# Configuration_JTAG.net
KiCad netlist of a schematic drawn in Altium Designer
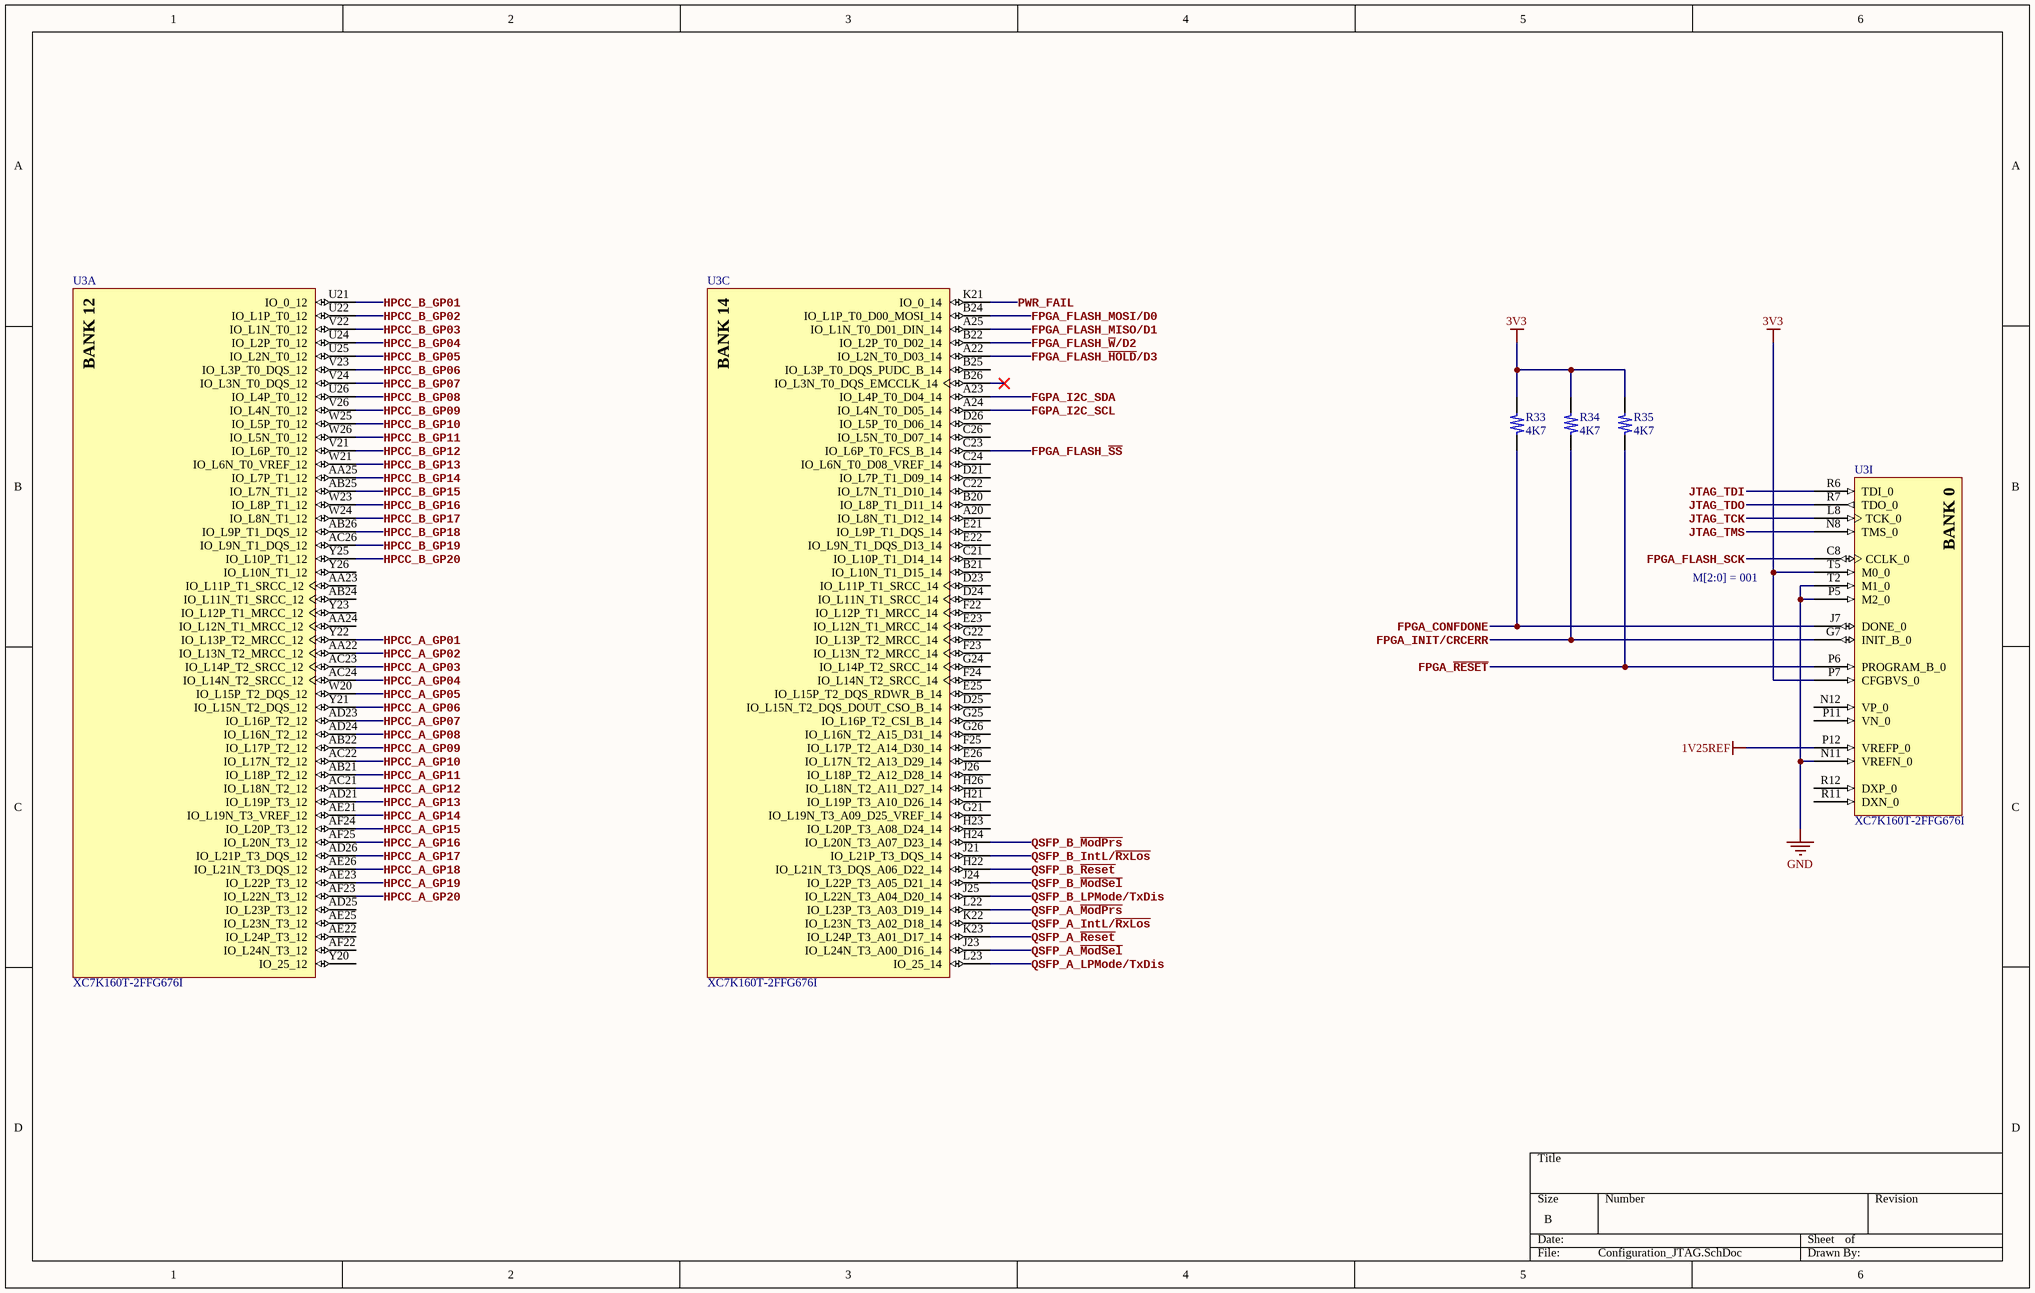
[diagram p0: Configuration_JTAG.SchDoc]

(export (version "E")
  (design (tool "Eeschema 10.0.6"))
  (components
    (comp (ref "R33")
      (value "4K7")
      (footprint "R_0402_Generic")
      (description "RES 4.7K OHM 1% 1/16W 0402")
      (libsource (lib "Capstone_Schematic_Library") (part "R_0402_Generic"))
    )
    (comp (ref "R34")
      (value "4K7")
      (footprint "R_0402_Generic")
      (description "RES 4.7K OHM 1% 1/16W 0402")
      (libsource (lib "Capstone_Schematic_Library") (part "R_0402_Generic"))
    )
    (comp (ref "R35")
      (value "4K7")
      (footprint "R_0402_Generic")
      (description "RES 4.7K OHM 1% 1/16W 0402")
      (libsource (lib "Capstone_Schematic_Library") (part "R_0402_Generic"))
    )
    (comp (ref "U3")
      (value "XC7K160T-2FFG676I")
      (footprint "FFG676_(XC7K160T-2FFG676I)")
      (description "Kintex-7 FPGA, 400 User I/Os, 8 GTX, 676-Ball BGA, Speed Grade 2, Industrial Grade, Pb-Free")
      (fields (field (name "GENERIC PART NUMBER") "XC7K160T") (field (name "MANUFACTURER") "Xilinx"))
      (libsource (lib "Capstone_Schematic_Library") (part "XC7K160T"))
    )
  )
  (nets
    (net (code "1") (name "/FGPA_I2C_SCL") (class "Default")
      (node (ref "U3") (pin "A24") (pinfunction "IO_L4N_T0_D05_14_A24") (pintype "bidirectional"))
    )
    (net (code "2") (name "/FGPA_I2C_SDA") (class "Default")
      (node (ref "U3") (pin "A23") (pinfunction "IO_L4P_T0_D04_14_A23") (pintype "bidirectional"))
    )
    (net (code "3") (name "/FPGA_CONFDONE") (class "Default")
      (node (ref "R33") (pin "1") (pinfunction "1_1") (pintype "passive"))
      (node (ref "U3") (pin "J7") (pinfunction "DONE_0_J7") (pintype "bidirectional"))
    )
    (net (code "4") (name "/FPGA_FLASH_MISO{slash}D1") (class "Default")
      (node (ref "U3") (pin "A25") (pinfunction "IO_L1N_T0_D01_DIN_14_A25") (pintype "bidirectional"))
    )
    (net (code "5") (name "/FPGA_FLASH_MOSI{slash}D0") (class "Default")
      (node (ref "U3") (pin "B24") (pinfunction "IO_L1P_T0_D00_MOSI_14_B24") (pintype "bidirectional"))
    )
    (net (code "6") (name "/FPGA_FLASH_SCK") (class "Default")
      (node (ref "U3") (pin "C8") (pinfunction "CCLK_0_C8") (pintype "bidirectional"))
    )
    (net (code "7") (name "/FPGA_FLASH_~{HOLD}{slash}D3") (class "Default")
      (node (ref "U3") (pin "A22") (pinfunction "IO_L2N_T0_D03_14_A22") (pintype "bidirectional"))
    )
    (net (code "8") (name "/FPGA_FLASH_~{SS}") (class "Default")
      (node (ref "U3") (pin "C23") (pinfunction "IO_L6P_T0_FCS_B_14_C23") (pintype "bidirectional"))
    )
    (net (code "9") (name "/FPGA_FLASH_~{W}{slash}D2") (class "Default")
      (node (ref "U3") (pin "B22") (pinfunction "IO_L2P_T0_D02_14_B22") (pintype "bidirectional"))
    )
    (net (code "10") (name "/FPGA_INIT{slash}CRCERR") (class "Default")
      (node (ref "R34") (pin "1") (pinfunction "1_1") (pintype "passive"))
      (node (ref "U3") (pin "G7") (pinfunction "INIT_B_0_G7") (pintype "bidirectional"))
    )
    (net (code "11") (name "/FPGA_~{RESET}") (class "Default")
      (node (ref "R35") (pin "1") (pinfunction "1_1") (pintype "passive"))
      (node (ref "U3") (pin "P6") (pinfunction "PROGRAM_B_0_P6") (pintype "input"))
    )
    (net (code "12") (name "/HPCC_A_GP01") (class "Default")
      (node (ref "U3") (pin "Y22") (pinfunction "IO_L13P_T2_MRCC_12_Y22") (pintype "bidirectional"))
    )
    (net (code "13") (name "/HPCC_A_GP02") (class "Default")
      (node (ref "U3") (pin "AA22") (pinfunction "IO_L13N_T2_MRCC_12_AA22") (pintype "bidirectional"))
    )
    (net (code "14") (name "/HPCC_A_GP03") (class "Default")
      (node (ref "U3") (pin "AC23") (pinfunction "IO_L14P_T2_SRCC_12_AC23") (pintype "bidirectional"))
    )
    (net (code "15") (name "/HPCC_A_GP04") (class "Default")
      (node (ref "U3") (pin "AC24") (pinfunction "IO_L14N_T2_SRCC_12_AC24") (pintype "bidirectional"))
    )
    (net (code "16") (name "/HPCC_A_GP05") (class "Default")
      (node (ref "U3") (pin "W20") (pinfunction "IO_L15P_T2_DQS_12_W20") (pintype "bidirectional"))
    )
    (net (code "17") (name "/HPCC_A_GP06") (class "Default")
      (node (ref "U3") (pin "Y21") (pinfunction "IO_L15N_T2_DQS_12_Y21") (pintype "bidirectional"))
    )
    (net (code "18") (name "/HPCC_A_GP07") (class "Default")
      (node (ref "U3") (pin "AD23") (pinfunction "IO_L16P_T2_12_AD23") (pintype "bidirectional"))
    )
    (net (code "19") (name "/HPCC_A_GP08") (class "Default")
      (node (ref "U3") (pin "AD24") (pinfunction "IO_L16N_T2_12_AD24") (pintype "bidirectional"))
    )
    (net (code "20") (name "/HPCC_A_GP09") (class "Default")
      (node (ref "U3") (pin "AB22") (pinfunction "IO_L17P_T2_12_AB22") (pintype "bidirectional"))
    )
    (net (code "21") (name "/HPCC_A_GP10") (class "Default")
      (node (ref "U3") (pin "AC22") (pinfunction "IO_L17N_T2_12_AC22") (pintype "bidirectional"))
    )
    (net (code "22") (name "/HPCC_A_GP11") (class "Default")
      (node (ref "U3") (pin "AB21") (pinfunction "IO_L18P_T2_12_AB21") (pintype "bidirectional"))
    )
    (net (code "23") (name "/HPCC_A_GP12") (class "Default")
      (node (ref "U3") (pin "AC21") (pinfunction "IO_L18N_T2_12_AC21") (pintype "bidirectional"))
    )
    (net (code "24") (name "/HPCC_A_GP13") (class "Default")
      (node (ref "U3") (pin "AD21") (pinfunction "IO_L19P_T3_12_AD21") (pintype "bidirectional"))
    )
    (net (code "25") (name "/HPCC_A_GP14") (class "Default")
      (node (ref "U3") (pin "AE21") (pinfunction "IO_L19N_T3_VREF_12_AE21") (pintype "bidirectional"))
    )
    (net (code "26") (name "/HPCC_A_GP15") (class "Default")
      (node (ref "U3") (pin "AF24") (pinfunction "IO_L20P_T3_12_AF24") (pintype "bidirectional"))
    )
    (net (code "27") (name "/HPCC_A_GP16") (class "Default")
      (node (ref "U3") (pin "AF25") (pinfunction "IO_L20N_T3_12_AF25") (pintype "bidirectional"))
    )
    (net (code "28") (name "/HPCC_A_GP17") (class "Default")
      (node (ref "U3") (pin "AD26") (pinfunction "IO_L21P_T3_DQS_12_AD26") (pintype "bidirectional"))
    )
    (net (code "29") (name "/HPCC_A_GP18") (class "Default")
      (node (ref "U3") (pin "AE26") (pinfunction "IO_L21N_T3_DQS_12_AE26") (pintype "bidirectional"))
    )
    (net (code "30") (name "/HPCC_A_GP19") (class "Default")
      (node (ref "U3") (pin "AE23") (pinfunction "IO_L22P_T3_12_AE23") (pintype "bidirectional"))
    )
    (net (code "31") (name "/HPCC_A_GP20") (class "Default")
      (node (ref "U3") (pin "AF23") (pinfunction "IO_L22N_T3_12_AF23") (pintype "bidirectional"))
    )
    (net (code "32") (name "/HPCC_B_GP01") (class "Default")
      (node (ref "U3") (pin "U21") (pinfunction "IO_0_12_U21") (pintype "bidirectional"))
    )
    (net (code "33") (name "/HPCC_B_GP02") (class "Default")
      (node (ref "U3") (pin "U22") (pinfunction "IO_L1P_T0_12_U22") (pintype "bidirectional"))
    )
    (net (code "34") (name "/HPCC_B_GP03") (class "Default")
      (node (ref "U3") (pin "V22") (pinfunction "IO_L1N_T0_12_V22") (pintype "bidirectional"))
    )
    (net (code "35") (name "/HPCC_B_GP04") (class "Default")
      (node (ref "U3") (pin "U24") (pinfunction "IO_L2P_T0_12_U24") (pintype "bidirectional"))
    )
    (net (code "36") (name "/HPCC_B_GP05") (class "Default")
      (node (ref "U3") (pin "U25") (pinfunction "IO_L2N_T0_12_U25") (pintype "bidirectional"))
    )
    (net (code "37") (name "/HPCC_B_GP06") (class "Default")
      (node (ref "U3") (pin "V23") (pinfunction "IO_L3P_T0_DQS_12_V23") (pintype "bidirectional"))
    )
    (net (code "38") (name "/HPCC_B_GP07") (class "Default")
      (node (ref "U3") (pin "V24") (pinfunction "IO_L3N_T0_DQS_12_V24") (pintype "bidirectional"))
    )
    (net (code "39") (name "/HPCC_B_GP08") (class "Default")
      (node (ref "U3") (pin "U26") (pinfunction "IO_L4P_T0_12_U26") (pintype "bidirectional"))
    )
    (net (code "40") (name "/HPCC_B_GP09") (class "Default")
      (node (ref "U3") (pin "V26") (pinfunction "IO_L4N_T0_12_V26") (pintype "bidirectional"))
    )
    (net (code "41") (name "/HPCC_B_GP10") (class "Default")
      (node (ref "U3") (pin "W25") (pinfunction "IO_L5P_T0_12_W25") (pintype "bidirectional"))
    )
    (net (code "42") (name "/HPCC_B_GP11") (class "Default")
      (node (ref "U3") (pin "W26") (pinfunction "IO_L5N_T0_12_W26") (pintype "bidirectional"))
    )
    (net (code "43") (name "/HPCC_B_GP12") (class "Default")
      (node (ref "U3") (pin "V21") (pinfunction "IO_L6P_T0_12_V21") (pintype "bidirectional"))
    )
    (net (code "44") (name "/HPCC_B_GP13") (class "Default")
      (node (ref "U3") (pin "W21") (pinfunction "IO_L6N_T0_VREF_12_W21") (pintype "bidirectional"))
    )
    (net (code "45") (name "/HPCC_B_GP14") (class "Default")
      (node (ref "U3") (pin "AA25") (pinfunction "IO_L7P_T1_12_AA25") (pintype "bidirectional"))
    )
    (net (code "46") (name "/HPCC_B_GP15") (class "Default")
      (node (ref "U3") (pin "AB25") (pinfunction "IO_L7N_T1_12_AB25") (pintype "bidirectional"))
    )
    (net (code "47") (name "/HPCC_B_GP16") (class "Default")
      (node (ref "U3") (pin "W23") (pinfunction "IO_L8P_T1_12_W23") (pintype "bidirectional"))
    )
    (net (code "48") (name "/HPCC_B_GP17") (class "Default")
      (node (ref "U3") (pin "W24") (pinfunction "IO_L8N_T1_12_W24") (pintype "bidirectional"))
    )
    (net (code "49") (name "/HPCC_B_GP18") (class "Default")
      (node (ref "U3") (pin "AB26") (pinfunction "IO_L9P_T1_DQS_12_AB26") (pintype "bidirectional"))
    )
    (net (code "50") (name "/HPCC_B_GP19") (class "Default")
      (node (ref "U3") (pin "AC26") (pinfunction "IO_L9N_T1_DQS_12_AC26") (pintype "bidirectional"))
    )
    (net (code "51") (name "/HPCC_B_GP20") (class "Default")
      (node (ref "U3") (pin "Y25") (pinfunction "IO_L10P_T1_12_Y25") (pintype "bidirectional"))
    )
    (net (code "52") (name "/JTAG_TCK") (class "Default")
      (node (ref "U3") (pin "L8") (pinfunction "TCK_0_L8") (pintype "input"))
    )
    (net (code "53") (name "/JTAG_TDI") (class "Default")
      (node (ref "U3") (pin "R6") (pinfunction "TDI_0_R6") (pintype "input"))
    )
    (net (code "54") (name "/JTAG_TDO") (class "Default")
      (node (ref "U3") (pin "R7") (pinfunction "TDO_0_R7") (pintype "output"))
    )
    (net (code "55") (name "/JTAG_TMS") (class "Default")
      (node (ref "U3") (pin "N8") (pinfunction "TMS_0_N8") (pintype "input"))
    )
    (net (code "56") (name "/PWR_FAIL") (class "Default")
      (node (ref "U3") (pin "K21") (pinfunction "IO_0_14_K21") (pintype "bidirectional"))
    )
    (net (code "57") (name "/QSFP_A_IntL{slash}~{RxLos}") (class "Default")
      (node (ref "U3") (pin "K22") (pinfunction "IO_L23N_T3_A02_D18_14_K22") (pintype "bidirectional"))
    )
    (net (code "58") (name "/QSFP_A_LPMode{slash}TxDis") (class "Default")
      (node (ref "U3") (pin "L23") (pinfunction "IO_25_14_L23") (pintype "bidirectional"))
    )
    (net (code "59") (name "/QSFP_A_~{ModPrs}") (class "Default")
      (node (ref "U3") (pin "L22") (pinfunction "IO_L23P_T3_A03_D19_14_L22") (pintype "bidirectional"))
    )
    (net (code "60") (name "/QSFP_A_~{ModSel}") (class "Default")
      (node (ref "U3") (pin "J23") (pinfunction "IO_L24N_T3_A00_D16_14_J23") (pintype "bidirectional"))
    )
    (net (code "61") (name "/QSFP_A_~{Reset}") (class "Default")
      (node (ref "U3") (pin "K23") (pinfunction "IO_L24P_T3_A01_D17_14_K23") (pintype "bidirectional"))
    )
    (net (code "62") (name "/QSFP_B_IntL{slash}~{RxLos}") (class "Default")
      (node (ref "U3") (pin "J21") (pinfunction "IO_L21P_T3_DQS_14_J21") (pintype "bidirectional"))
    )
    (net (code "63") (name "/QSFP_B_LPMode{slash}TxDis") (class "Default")
      (node (ref "U3") (pin "J25") (pinfunction "IO_L22N_T3_A04_D20_14_J25") (pintype "bidirectional"))
    )
    (net (code "64") (name "/QSFP_B_~{ModPrs}") (class "Default")
      (node (ref "U3") (pin "H24") (pinfunction "IO_L20N_T3_A07_D23_14_H24") (pintype "bidirectional"))
    )
    (net (code "65") (name "/QSFP_B_~{ModSel}") (class "Default")
      (node (ref "U3") (pin "J24") (pinfunction "IO_L22P_T3_A05_D21_14_J24") (pintype "bidirectional"))
    )
    (net (code "66") (name "/QSFP_B_~{Reset}") (class "Default")
      (node (ref "U3") (pin "H22") (pinfunction "IO_L21N_T3_DQS_A06_D22_14_H22") (pintype "bidirectional"))
    )
    (net (code "67") (name "1V25REF") (class "Default")
      (node (ref "U3") (pin "P12") (pinfunction "VREFP_0_P12") (pintype "input"))
    )
    (net (code "68") (name "3V3") (class "Default")
      (node (ref "R33") (pin "2") (pinfunction "2_2") (pintype "passive"))
      (node (ref "R34") (pin "2") (pinfunction "2_2") (pintype "passive"))
      (node (ref "R35") (pin "2") (pinfunction "2_2") (pintype "passive"))
      (node (ref "U3") (pin "P7") (pinfunction "CFGBVS_0_P7") (pintype "input"))
      (node (ref "U3") (pin "T5") (pinfunction "M0_0_T5") (pintype "input"))
    )
    (net (code "69") (name "GND") (class "Default")
      (node (ref "U3") (pin "N11") (pinfunction "VREFN_0_N11") (pintype "input"))
      (node (ref "U3") (pin "P5") (pinfunction "M2_0_P5") (pintype "input"))
      (node (ref "U3") (pin "T2") (pinfunction "M1_0_T2") (pintype "input"))
    )
    (net (code "70") (name "unconnected-(U3A-IO_25_12-PadY20)") (class "Default")
      (node (ref "U3") (pin "Y20") (pinfunction "IO_25_12_Y20") (pintype "bidirectional"))
    )
    (net (code "71") (name "unconnected-(U3A-IO_L10N_T1_12-PadY26)") (class "Default")
      (node (ref "U3") (pin "Y26") (pinfunction "IO_L10N_T1_12_Y26") (pintype "bidirectional"))
    )
    (net (code "72") (name "unconnected-(U3A-IO_L11N_T1_SRCC_12-PadAB24)") (class "Default")
      (node (ref "U3") (pin "AB24") (pinfunction "IO_L11N_T1_SRCC_12_AB24") (pintype "bidirectional"))
    )
    (net (code "73") (name "unconnected-(U3A-IO_L11P_T1_SRCC_12-PadAA23)") (class "Default")
      (node (ref "U3") (pin "AA23") (pinfunction "IO_L11P_T1_SRCC_12_AA23") (pintype "bidirectional"))
    )
    (net (code "74") (name "unconnected-(U3A-IO_L12N_T1_MRCC_12-PadAA24)") (class "Default")
      (node (ref "U3") (pin "AA24") (pinfunction "IO_L12N_T1_MRCC_12_AA24") (pintype "bidirectional"))
    )
    (net (code "75") (name "unconnected-(U3A-IO_L12P_T1_MRCC_12-PadY23)") (class "Default")
      (node (ref "U3") (pin "Y23") (pinfunction "IO_L12P_T1_MRCC_12_Y23") (pintype "bidirectional"))
    )
    (net (code "76") (name "unconnected-(U3A-IO_L23N_T3_12-PadAE25)") (class "Default")
      (node (ref "U3") (pin "AE25") (pinfunction "IO_L23N_T3_12_AE25") (pintype "bidirectional"))
    )
    (net (code "77") (name "unconnected-(U3A-IO_L23P_T3_12-PadAD25)") (class "Default")
      (node (ref "U3") (pin "AD25") (pinfunction "IO_L23P_T3_12_AD25") (pintype "bidirectional"))
    )
    (net (code "78") (name "unconnected-(U3A-IO_L24N_T3_12-PadAF22)") (class "Default")
      (node (ref "U3") (pin "AF22") (pinfunction "IO_L24N_T3_12_AF22") (pintype "bidirectional"))
    )
    (net (code "79") (name "unconnected-(U3A-IO_L24P_T3_12-PadAE22)") (class "Default")
      (node (ref "U3") (pin "AE22") (pinfunction "IO_L24P_T3_12_AE22") (pintype "bidirectional"))
    )
    (net (code "80") (name "unconnected-(U3C-IO_L3N_T0_DQS_EMCCLK_14-PadB26)") (class "Default")
      (node (ref "U3") (pin "B26") (pinfunction "IO_L3N_T0_DQS_EMCCLK_14_B26") (pintype "bidirectional+no_connect"))
    )
    (net (code "81") (name "unconnected-(U3C-IO_L3P_T0_DQS_PUDC_B_14-PadB25)") (class "Default")
      (node (ref "U3") (pin "B25") (pinfunction "IO_L3P_T0_DQS_PUDC_B_14_B25") (pintype "bidirectional"))
    )
    (net (code "82") (name "unconnected-(U3C-IO_L5N_T0_D07_14-PadC26)") (class "Default")
      (node (ref "U3") (pin "C26") (pinfunction "IO_L5N_T0_D07_14_C26") (pintype "bidirectional"))
    )
    (net (code "83") (name "unconnected-(U3C-IO_L5P_T0_D06_14-PadD26)") (class "Default")
      (node (ref "U3") (pin "D26") (pinfunction "IO_L5P_T0_D06_14_D26") (pintype "bidirectional"))
    )
    (net (code "84") (name "unconnected-(U3C-IO_L6N_T0_D08_VREF_14-PadC24)") (class "Default")
      (node (ref "U3") (pin "C24") (pinfunction "IO_L6N_T0_D08_VREF_14_C24") (pintype "bidirectional"))
    )
    (net (code "85") (name "unconnected-(U3C-IO_L7N_T1_D10_14-PadC22)") (class "Default")
      (node (ref "U3") (pin "C22") (pinfunction "IO_L7N_T1_D10_14_C22") (pintype "bidirectional"))
    )
    (net (code "86") (name "unconnected-(U3C-IO_L7P_T1_D09_14-PadD21)") (class "Default")
      (node (ref "U3") (pin "D21") (pinfunction "IO_L7P_T1_D09_14_D21") (pintype "bidirectional"))
    )
    (net (code "87") (name "unconnected-(U3C-IO_L8N_T1_D12_14-PadA20)") (class "Default")
      (node (ref "U3") (pin "A20") (pinfunction "IO_L8N_T1_D12_14_A20") (pintype "bidirectional"))
    )
    (net (code "88") (name "unconnected-(U3C-IO_L8P_T1_D11_14-PadB20)") (class "Default")
      (node (ref "U3") (pin "B20") (pinfunction "IO_L8P_T1_D11_14_B20") (pintype "bidirectional"))
    )
    (net (code "89") (name "unconnected-(U3C-IO_L9N_T1_DQS_D13_14-PadE22)") (class "Default")
      (node (ref "U3") (pin "E22") (pinfunction "IO_L9N_T1_DQS_D13_14_E22") (pintype "bidirectional"))
    )
    (net (code "90") (name "unconnected-(U3C-IO_L9P_T1_DQS_14-PadE21)") (class "Default")
      (node (ref "U3") (pin "E21") (pinfunction "IO_L9P_T1_DQS_14_E21") (pintype "bidirectional"))
    )
    (net (code "91") (name "unconnected-(U3C-IO_L10N_T1_D15_14-PadB21)") (class "Default")
      (node (ref "U3") (pin "B21") (pinfunction "IO_L10N_T1_D15_14_B21") (pintype "bidirectional"))
    )
    (net (code "92") (name "unconnected-(U3C-IO_L10P_T1_D14_14-PadC21)") (class "Default")
      (node (ref "U3") (pin "C21") (pinfunction "IO_L10P_T1_D14_14_C21") (pintype "bidirectional"))
    )
    (net (code "93") (name "unconnected-(U3C-IO_L11N_T1_SRCC_14-PadD24)") (class "Default")
      (node (ref "U3") (pin "D24") (pinfunction "IO_L11N_T1_SRCC_14_D24") (pintype "bidirectional"))
    )
    (net (code "94") (name "unconnected-(U3C-IO_L11P_T1_SRCC_14-PadD23)") (class "Default")
      (node (ref "U3") (pin "D23") (pinfunction "IO_L11P_T1_SRCC_14_D23") (pintype "bidirectional"))
    )
    (net (code "95") (name "unconnected-(U3C-IO_L12N_T1_MRCC_14-PadE23)") (class "Default")
      (node (ref "U3") (pin "E23") (pinfunction "IO_L12N_T1_MRCC_14_E23") (pintype "bidirectional"))
    )
    (net (code "96") (name "unconnected-(U3C-IO_L12P_T1_MRCC_14-PadF22)") (class "Default")
      (node (ref "U3") (pin "F22") (pinfunction "IO_L12P_T1_MRCC_14_F22") (pintype "bidirectional"))
    )
    (net (code "97") (name "unconnected-(U3C-IO_L13N_T2_MRCC_14-PadF23)") (class "Default")
      (node (ref "U3") (pin "F23") (pinfunction "IO_L13N_T2_MRCC_14_F23") (pintype "bidirectional"))
    )
    (net (code "98") (name "unconnected-(U3C-IO_L13P_T2_MRCC_14-PadG22)") (class "Default")
      (node (ref "U3") (pin "G22") (pinfunction "IO_L13P_T2_MRCC_14_G22") (pintype "bidirectional"))
    )
    (net (code "99") (name "unconnected-(U3C-IO_L14N_T2_SRCC_14-PadF24)") (class "Default")
      (node (ref "U3") (pin "F24") (pinfunction "IO_L14N_T2_SRCC_14_F24") (pintype "bidirectional"))
    )
    (net (code "100") (name "unconnected-(U3C-IO_L14P_T2_SRCC_14-PadG24)") (class "Default")
      (node (ref "U3") (pin "G24") (pinfunction "IO_L14P_T2_SRCC_14_G24") (pintype "bidirectional"))
    )
    (net (code "101") (name "unconnected-(U3C-IO_L15N_T2_DQS_DOUT_CSO_B_14-PadD25)") (class "Default")
      (node (ref "U3") (pin "D25") (pinfunction "IO_L15N_T2_DQS_DOUT_CSO_B_14_D25") (pintype "bidirectional"))
    )
    (net (code "102") (name "unconnected-(U3C-IO_L15P_T2_DQS_RDWR_B_14-PadE25)") (class "Default")
      (node (ref "U3") (pin "E25") (pinfunction "IO_L15P_T2_DQS_RDWR_B_14_E25") (pintype "bidirectional"))
    )
    (net (code "103") (name "unconnected-(U3C-IO_L16N_T2_A15_D31_14-PadG26)") (class "Default")
      (node (ref "U3") (pin "G26") (pinfunction "IO_L16N_T2_A15_D31_14_G26") (pintype "bidirectional"))
    )
    (net (code "104") (name "unconnected-(U3C-IO_L16P_T2_CSI_B_14-PadG25)") (class "Default")
      (node (ref "U3") (pin "G25") (pinfunction "IO_L16P_T2_CSI_B_14_G25") (pintype "bidirectional"))
    )
    (net (code "105") (name "unconnected-(U3C-IO_L17N_T2_A13_D29_14-PadE26)") (class "Default")
      (node (ref "U3") (pin "E26") (pinfunction "IO_L17N_T2_A13_D29_14_E26") (pintype "bidirectional"))
    )
    (net (code "106") (name "unconnected-(U3C-IO_L17P_T2_A14_D30_14-PadF25)") (class "Default")
      (node (ref "U3") (pin "F25") (pinfunction "IO_L17P_T2_A14_D30_14_F25") (pintype "bidirectional"))
    )
    (net (code "107") (name "unconnected-(U3C-IO_L18N_T2_A11_D27_14-PadH26)") (class "Default")
      (node (ref "U3") (pin "H26") (pinfunction "IO_L18N_T2_A11_D27_14_H26") (pintype "bidirectional"))
    )
    (net (code "108") (name "unconnected-(U3C-IO_L18P_T2_A12_D28_14-PadJ26)") (class "Default")
      (node (ref "U3") (pin "J26") (pinfunction "IO_L18P_T2_A12_D28_14_J26") (pintype "bidirectional"))
    )
    (net (code "109") (name "unconnected-(U3C-IO_L19N_T3_A09_D25_VREF_14-PadG21)") (class "Default")
      (node (ref "U3") (pin "G21") (pinfunction "IO_L19N_T3_A09_D25_VREF_14_G21") (pintype "bidirectional"))
    )
    (net (code "110") (name "unconnected-(U3C-IO_L19P_T3_A10_D26_14-PadH21)") (class "Default")
      (node (ref "U3") (pin "H21") (pinfunction "IO_L19P_T3_A10_D26_14_H21") (pintype "bidirectional"))
    )
    (net (code "111") (name "unconnected-(U3C-IO_L20P_T3_A08_D24_14-PadH23)") (class "Default")
      (node (ref "U3") (pin "H23") (pinfunction "IO_L20P_T3_A08_D24_14_H23") (pintype "bidirectional"))
    )
    (net (code "112") (name "unconnected-(U3I-DXN_0-PadR11)") (class "Default")
      (node (ref "U3") (pin "R11") (pinfunction "DXN_0_R11") (pintype "input"))
    )
    (net (code "113") (name "unconnected-(U3I-DXP_0-PadR12)") (class "Default")
      (node (ref "U3") (pin "R12") (pinfunction "DXP_0_R12") (pintype "input"))
    )
    (net (code "114") (name "unconnected-(U3I-VN_0-PadP11)") (class "Default")
      (node (ref "U3") (pin "P11") (pinfunction "VN_0_P11") (pintype "input"))
    )
    (net (code "115") (name "unconnected-(U3I-VP_0-PadN12)") (class "Default")
      (node (ref "U3") (pin "N12") (pinfunction "VP_0_N12") (pintype "input"))
    )
  )
)
